# flash_modchip.net
KiCad netlist of a schematic drawn in EAGLE
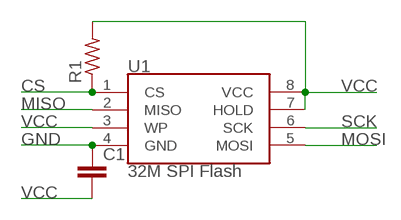
[diagram p0: schematic, sheet 1]

(export (version "E")
  (design (tool "Eeschema 10.0.6"))
  (components
    (comp (ref "C1")
      (value "C-EUC0402")
      (footprint "eagle-import:C0402")
      (libsource (lib "eagle-import") (part "C-EUC0402"))
    )
    (comp (ref "R1")
      (value "R-US_R0402")
      (footprint "eagle-import:R0402")
      (libsource (lib "eagle-import") (part "R-US_R0402"))
    )
    (comp (ref "U1")
      (value "32M SPI Flash")
      (footprint "eagle-import:SO08")
      (libsource (lib "eagle-import") (part "SPI_FLASH-X25XXSMD"))
    )
  )
  (nets
    (net (code "1") (name "/CS") (class "Default")
      (node (ref "R1") (pin "1") (pinfunction "1_1") (pintype "passive"))
      (node (ref "U1") (pin "1") (pinfunction "CS_1") (pintype "bidirectional"))
    )
    (net (code "2") (name "/GND") (class "Default")
      (node (ref "C1") (pin "1") (pinfunction "1_1") (pintype "passive"))
      (node (ref "U1") (pin "4") (pinfunction "GND_4") (pintype "power_in"))
    )
    (net (code "3") (name "/MISO") (class "Default")
      (node (ref "U1") (pin "2") (pinfunction "MISO_2") (pintype "bidirectional"))
    )
    (net (code "4") (name "/MOSI") (class "Default")
      (node (ref "U1") (pin "5") (pinfunction "MOSI_5") (pintype "bidirectional"))
    )
    (net (code "5") (name "/SCK") (class "Default")
      (node (ref "U1") (pin "6") (pinfunction "SCK_6") (pintype "bidirectional"))
    )
    (net (code "6") (name "/VCC") (class "Default")
      (node (ref "C1") (pin "2") (pinfunction "2_2") (pintype "passive"))
      (node (ref "R1") (pin "2") (pinfunction "2_2") (pintype "passive"))
      (node (ref "U1") (pin "3") (pinfunction "WP_3") (pintype "bidirectional"))
      (node (ref "U1") (pin "7") (pinfunction "HOLD_7") (pintype "bidirectional"))
      (node (ref "U1") (pin "8") (pinfunction "VCC_8") (pintype "power_in"))
    )
  )
)
